# Current_Sensor.net
KiCad netlist of a schematic drawn in Altium Designer
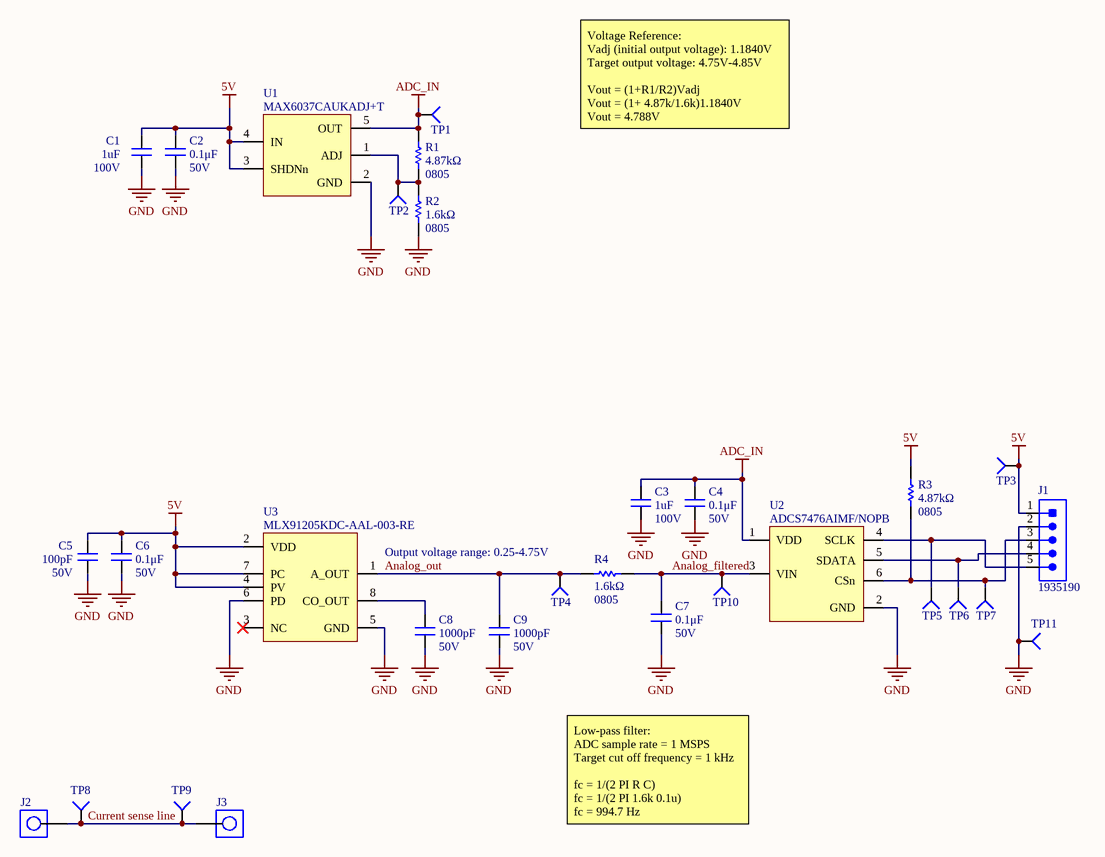
[diagram p0: Current Sensor.SchDoc]

(export (version "E")
  (design (tool "Eeschema 10.0.6"))
  (components
    (comp (ref "C1")
      (value "CAP_1uF_100V_1206")
      (footprint "CAPC3216X190X50NL20T25")
      (description "CAP CER 1UF 100V X7R 1206")
      (fields
        (field (name "MANUFACTURER") "Murata")
        (field (name "MANUFACTURER PART NUMBER") "GCJ31CR72A105KA01L")
        (field (name "CAPACITANCE") "1uF")
        (field (name "VOLTAGE RATING") "100V")
      )
      (libsource (lib "UWRT_Schematic_Library_2020") (part "CAP_1uF_100V_1206"))
    )
    (comp (ref "C2")
      (value "0.1μF")
      (footprint "CAP2012")
      (description "CAP CER 0.1UF 50V X7R 0805")
      (fields (field (name "TOLERANCE") "10%") (field (name "VOLTAGE RATING") "50V"))
      (libsource (lib "UWRT_Schematic_Library_2020") (part "CAP_0.1uF_50V_0805"))
    )
    (comp (ref "C3")
      (value "CAP_1uF_100V_1206")
      (footprint "CAPC3216X190X50NL20T25")
      (description "CAP CER 1UF 100V X7R 1206")
      (fields
        (field (name "MANUFACTURER") "Murata")
        (field (name "MANUFACTURER PART NUMBER") "GCJ31CR72A105KA01L")
        (field (name "CAPACITANCE") "1uF")
        (field (name "VOLTAGE RATING") "100V")
      )
      (libsource (lib "UWRT_Schematic_Library_2020") (part "CAP_1uF_100V_1206"))
    )
    (comp (ref "C4")
      (value "0.1μF")
      (footprint "CAP2012")
      (description "CAP CER 0.1UF 50V X7R 0805")
      (fields (field (name "TOLERANCE") "10%") (field (name "VOLTAGE RATING") "50V"))
      (libsource (lib "UWRT_Schematic_Library_2020") (part "CAP_0.1uF_50V_0805"))
    )
    (comp (ref "C5")
      (value "100pF")
      (footprint "CAP2012")
      (description "CAP CER 100PF 50V C0G/NP0 0805")
      (fields
        (field (name "TOLERANCE") "5%")
        (field (name "VOLTAGE RATING") "50V")
        (field (name "Comment") "CAP_100pF_50V_0805")
      )
      (libsource (lib "UWRT_Schematic_Library_2020") (part "CAP_100pF_50V_0805"))
    )
    (comp (ref "C6")
      (value "0.1μF")
      (footprint "CAP2012")
      (description "CAP CER 0.1UF 50V X7R 0805")
      (fields (field (name "TOLERANCE") "10%") (field (name "VOLTAGE RATING") "50V"))
      (libsource (lib "UWRT_Schematic_Library_2020") (part "CAP_0.1uF_50V_0805"))
    )
    (comp (ref "C7")
      (value "0.1μF")
      (footprint "CAP2012")
      (description "CAP CER 0.1UF 50V X7R 0805")
      (fields (field (name "TOLERANCE") "10%") (field (name "VOLTAGE RATING") "50V"))
      (libsource (lib "UWRT_Schematic_Library_2020") (part "CAP_0.1uF_50V_0805"))
    )
    (comp (ref "C8")
      (value "CAP_1000pF_50V_0805")
      (footprint "CAP2012")
      (description "CAP CER 1000pF 50V X7R 0805")
      (fields
        (field (name "TOLERANCE") "10%")
        (field (name "VOLTAGE") "50V")
        (field (name "VOLTAGE RATING") "50V")
        (field (name "CAPACITANCE") "1000pF")
      )
      (libsource (lib "UWRT_Schematic_Library_2020") (part "CAP_1000pF_50V_0805"))
    )
    (comp (ref "C9")
      (value "CAP_1000pF_50V_0805")
      (footprint "CAP2012")
      (description "CAP CER 1000pF 50V X7R 0805")
      (fields
        (field (name "TOLERANCE") "10%")
        (field (name "VOLTAGE") "50V")
        (field (name "VOLTAGE RATING") "50V")
        (field (name "CAPACITANCE") "1000pF")
      )
      (libsource (lib "UWRT_Schematic_Library_2020") (part "CAP_1000pF_50V_0805"))
    )
    (comp (ref "J1")
      (value "CON_5M_TERM")
      (footprint "1935190")
      (description "Barrier Strip Terminal Block, 17.5A, 1.5mm2, 1 Row(s), 1 Deck(s)")
      (fields (field (name "VOLTAGE") "300V") (field (name "MANUFACTURER PART NUMBER 1") "1935190"))
      (libsource (lib "UWRT_Schematic_Library_2020") (part "CON_5M_TERM"))
    )
    (comp (ref "J2")
      (value "Screw Terminal 6-32")
      (footprint "7701_KEYSTONE")
      (description "TERM W/ASSEMBLD SCREW VERT PCMNT")
      (libsource (lib "UWRT_Schematic_Library_2020") (part "SCREW_TERMINAL_1_POS_6_32"))
    )
    (comp (ref "J3")
      (value "Screw Terminal 6-32")
      (footprint "7701_KEYSTONE")
      (description "TERM W/ASSEMBLD SCREW VERT PCMNT")
      (libsource (lib "UWRT_Schematic_Library_2020") (part "SCREW_TERMINAL_1_POS_6_32"))
    )
    (comp (ref "R1")
      (value "RES_4.87kΩ_0805")
      (footprint "RESC0805(2012)_H")
      (description "RES SMD 4.87k OHM 0.1% 1/8W 0805")
      (fields
        (field (name "TOLERANCE") "0.1%")
        (field (name "CASE CODE (IMPERIAL)") "0805")
        (field (name "RESISTANCE") "4.87kΩ")
      )
      (libsource (lib "UWRT_Schematic_Library_2020") (part "RES_4.87kΩ_0805"))
    )
    (comp (ref "R2")
      (value "RES_1.6kΩ_0805")
      (footprint "RESC0805(2012)_H")
      (description "RES SMD 1.6K OHM 0.1% 1/4W 0805")
      (fields
        (field (name "TOLERANCE") "0.1%")
        (field (name "CASE/PACKAGE") "0805")
        (field (name "RESISTANCE") "1.6kΩ")
      )
      (libsource (lib "UWRT_Schematic_Library_2020") (part "RES_1.6kΩ_0805"))
    )
    (comp (ref "R3")
      (value "RES_4.87kΩ_0805")
      (footprint "RESC0805(2012)_H")
      (description "RES SMD 4.87k OHM 0.1% 1/8W 0805")
      (fields
        (field (name "TOLERANCE") "0.1%")
        (field (name "CASE CODE (IMPERIAL)") "0805")
        (field (name "RESISTANCE") "4.87kΩ")
      )
      (libsource (lib "UWRT_Schematic_Library_2020") (part "RES_4.87kΩ_0805"))
    )
    (comp (ref "R4")
      (value "RES_1.6kΩ_0805")
      (footprint "RESC0805(2012)_H")
      (description "RES SMD 1.6K OHM 0.1% 1/4W 0805")
      (fields
        (field (name "TOLERANCE") "0.1%")
        (field (name "CASE/PACKAGE") "0805")
        (field (name "RESISTANCE") "1.6kΩ")
      )
      (libsource (lib "UWRT_Schematic_Library_2020") (part "RES_1.6kΩ_0805"))
    )
    (comp (ref "TP1")
      (value "TESTPOINT_SMD_LOOP")
      (footprint "S1751-46R")
      (description "PC TEST POINT SMD")
      (libsource (lib "UWRT_Schematic_Library_2020") (part "TESTPOINT_SMD_LOOP"))
    )
    (comp (ref "TP2")
      (value "TESTPOINT_1MM_CIRCLE")
      (footprint "TESTPOINT_CIRCLE_1MM")
      (description "TESTPOINT 1MM CIRCLE")
      (libsource (lib "UWRT_Schematic_Library_2020") (part "TESTPOINT_1MM_CIRCLE"))
    )
    (comp (ref "TP3")
      (value "TESTPOINT_SMD_LOOP")
      (footprint "S1751-46R")
      (description "PC TEST POINT SMD")
      (libsource (lib "UWRT_Schematic_Library_2020") (part "TESTPOINT_SMD_LOOP"))
    )
    (comp (ref "TP4")
      (value "TESTPOINT_1MM_CIRCLE")
      (footprint "TESTPOINT_CIRCLE_1MM")
      (description "TESTPOINT 1MM CIRCLE")
      (libsource (lib "UWRT_Schematic_Library_2020") (part "TESTPOINT_1MM_CIRCLE"))
    )
    (comp (ref "TP5")
      (value "TESTPOINT_1MM_CIRCLE")
      (footprint "TESTPOINT_CIRCLE_1MM")
      (description "TESTPOINT 1MM CIRCLE")
      (libsource (lib "UWRT_Schematic_Library_2020") (part "TESTPOINT_1MM_CIRCLE"))
    )
    (comp (ref "TP6")
      (value "TESTPOINT_1MM_CIRCLE")
      (footprint "TESTPOINT_CIRCLE_1MM")
      (description "TESTPOINT 1MM CIRCLE")
      (libsource (lib "UWRT_Schematic_Library_2020") (part "TESTPOINT_1MM_CIRCLE"))
    )
    (comp (ref "TP7")
      (value "TESTPOINT_1MM_CIRCLE")
      (footprint "TESTPOINT_CIRCLE_1MM")
      (description "TESTPOINT 1MM CIRCLE")
      (libsource (lib "UWRT_Schematic_Library_2020") (part "TESTPOINT_1MM_CIRCLE"))
    )
    (comp (ref "TP8")
      (value "TESTPOINT_SMD_LOOP")
      (footprint "S1751-46R")
      (description "PC TEST POINT SMD")
      (libsource (lib "UWRT_Schematic_Library_2020") (part "TESTPOINT_SMD_LOOP"))
    )
    (comp (ref "TP9")
      (value "TESTPOINT_SMD_LOOP")
      (footprint "S1751-46R")
      (description "PC TEST POINT SMD")
      (libsource (lib "UWRT_Schematic_Library_2020") (part "TESTPOINT_SMD_LOOP"))
    )
    (comp (ref "TP10")
      (value "TESTPOINT_1MM_CIRCLE")
      (footprint "TESTPOINT_CIRCLE_1MM")
      (description "TESTPOINT 1MM CIRCLE")
      (libsource (lib "UWRT_Schematic_Library_2020") (part "TESTPOINT_1MM_CIRCLE"))
    )
    (comp (ref "TP11")
      (value "TESTPOINT_1MM_SQUARE")
      (footprint "TESTPOINT_SQUARE_1MM")
      (description "TESTPOINT 1MM SQUARE")
      (libsource (lib "UWRT_Schematic_Library_2020") (part "TESTPOINT_1MM_SQUARE"))
    )
    (comp (ref "U1")
      (value "MAX6037CAUKADJ+T")
      (footprint "SOT23-5")
      (description "Three Terminal Voltage Reference, 1 Output, Trim/Adjustable, BICMOS, PDSO5")
      (fields
        (field (name "TOLERANCE") "0.5%")
        (field (name "MANUFACTURER PART NUMBER 1") "MAX6037CAUKADJ+T")
      )
      (libsource (lib "UWRT_Schematic_Library_2020") (part "MAX6037CAUKADJ+T"))
    )
    (comp (ref "U2")
      (value "ADCS7476AIMF/NOPB")
      (footprint "ADCS747x")
      (description "1-Channel Single ADC SAR 1Msps 12-bit Serial 6-Pin SOT-23 T/R")
      (fields (field (name "MANUFACTURER PART NUMBER 1") "ADCS7476AIMF/NOPB"))
      (libsource (lib "UWRT_Schematic_Library_2020") (part "ADCS7476AIMF/NOPB"))
    )
    (comp (ref "U3")
      (value "MLX91205KDC-AAL-003-RE")
      (footprint "8-SOIC_M")
      (description "Analog Circuit, 1 Func, PDSO8")
      (fields (field (name "MANUFACTURER PART NUMBER 1") "MLX91205KDC-AAL-003-RE"))
      (libsource (lib "UWRT_Schematic_Library_2020") (part "MLX91205KDC-AAL-003-RE"))
    )
  )
  (nets
    (net (code "1") (name "/Analog_filtered") (class "Default")
      (node (ref "C7") (pin "2") (pinfunction "2_2") (pintype "passive"))
      (node (ref "R4") (pin "1") (pinfunction "1_1") (pintype "passive"))
      (node (ref "TP10") (pin "1") (pinfunction "=value_1") (pintype "passive"))
      (node (ref "U2") (pin "3") (pinfunction "VIN_3") (pintype "passive"))
    )
    (net (code "2") (name "/Analog_out") (class "Default")
      (node (ref "C9") (pin "2") (pinfunction "2_2") (pintype "passive"))
      (node (ref "R4") (pin "2") (pinfunction "2_2") (pintype "passive"))
      (node (ref "TP4") (pin "1") (pinfunction "=value_1") (pintype "passive"))
      (node (ref "U3") (pin "1") (pinfunction "A_OUT_1") (pintype "passive"))
    )
    (net (code "3") (name "/Current sense line") (class "Default")
      (node (ref "J2") (pin "1") (pinfunction "1_1") (pintype "passive"))
      (node (ref "J3") (pin "1") (pinfunction "1_1") (pintype "passive"))
      (node (ref "TP8") (pin "1") (pinfunction "=value_1") (pintype "passive"))
      (node (ref "TP9") (pin "1") (pinfunction "=value_1") (pintype "passive"))
    )
    (net (code "4") (name "5V") (class "Default")
      (node (ref "C1") (pin "2") (pinfunction "2_2") (pintype "passive"))
      (node (ref "C2") (pin "2") (pinfunction "2_2") (pintype "passive"))
      (node (ref "C5") (pin "2") (pinfunction "2_2") (pintype "passive"))
      (node (ref "C6") (pin "2") (pinfunction "2_2") (pintype "passive"))
      (node (ref "J1") (pin "1") (pinfunction "1_1") (pintype "passive"))
      (node (ref "R3") (pin "2") (pinfunction "2_2") (pintype "passive"))
      (node (ref "TP3") (pin "1") (pinfunction "=value_1") (pintype "passive"))
      (node (ref "U1") (pin "3") (pinfunction "SHDNn_3") (pintype "passive"))
      (node (ref "U1") (pin "4") (pinfunction "IN_4") (pintype "passive"))
      (node (ref "U3") (pin "2") (pinfunction "VDD_2") (pintype "passive"))
      (node (ref "U3") (pin "4") (pinfunction "PV_4") (pintype "passive"))
      (node (ref "U3") (pin "7") (pinfunction "PC_7") (pintype "passive"))
    )
    (net (code "5") (name "ADC_IN") (class "Default")
      (node (ref "C3") (pin "2") (pinfunction "2_2") (pintype "passive"))
      (node (ref "C4") (pin "2") (pinfunction "2_2") (pintype "passive"))
      (node (ref "R1") (pin "2") (pinfunction "2_2") (pintype "passive"))
      (node (ref "TP1") (pin "1") (pinfunction "=value_1") (pintype "passive"))
      (node (ref "U1") (pin "5") (pinfunction "OUT_5") (pintype "passive"))
      (node (ref "U2") (pin "1") (pinfunction "VDD_1") (pintype "passive"))
    )
    (net (code "6") (name "GND") (class "Default")
      (node (ref "C1") (pin "1") (pinfunction "1_1") (pintype "passive"))
      (node (ref "C2") (pin "1") (pinfunction "1_1") (pintype "passive"))
      (node (ref "C3") (pin "1") (pinfunction "1_1") (pintype "passive"))
      (node (ref "C4") (pin "1") (pinfunction "1_1") (pintype "passive"))
      (node (ref "C5") (pin "1") (pinfunction "1_1") (pintype "passive"))
      (node (ref "C6") (pin "1") (pinfunction "1_1") (pintype "passive"))
      (node (ref "C7") (pin "1") (pinfunction "1_1") (pintype "passive"))
      (node (ref "C8") (pin "1") (pinfunction "1_1") (pintype "passive"))
      (node (ref "C9") (pin "1") (pinfunction "1_1") (pintype "passive"))
      (node (ref "J1") (pin "2") (pinfunction "2_2") (pintype "passive"))
      (node (ref "R2") (pin "1") (pinfunction "1_1") (pintype "passive"))
      (node (ref "TP11") (pin "1") (pinfunction "=value_1") (pintype "passive"))
      (node (ref "U1") (pin "2") (pinfunction "GND_2") (pintype "passive"))
      (node (ref "U2") (pin "2") (pinfunction "GND_2") (pintype "passive"))
      (node (ref "U3") (pin "5") (pinfunction "GND_5") (pintype "passive"))
      (node (ref "U3") (pin "6") (pinfunction "PD_6") (pintype "passive"))
    )
    (net (code "7") (name "Net-(TP2-=value)") (class "Default")
      (node (ref "R1") (pin "1") (pinfunction "1_1") (pintype "passive"))
      (node (ref "R2") (pin "2") (pinfunction "2_2") (pintype "passive"))
      (node (ref "TP2") (pin "1") (pinfunction "=value_1") (pintype "passive"))
      (node (ref "U1") (pin "1") (pinfunction "ADJ_1") (pintype "passive"))
    )
    (net (code "8") (name "Net-(TP5-=value)") (class "Default")
      (node (ref "J1") (pin "5") (pinfunction "5_5") (pintype "passive"))
      (node (ref "TP5") (pin "1") (pinfunction "=value_1") (pintype "passive"))
      (node (ref "U2") (pin "4") (pinfunction "SCLK_4") (pintype "passive"))
    )
    (net (code "9") (name "Net-(TP6-=value)") (class "Default")
      (node (ref "J1") (pin "4") (pinfunction "4_4") (pintype "passive"))
      (node (ref "TP6") (pin "1") (pinfunction "=value_1") (pintype "passive"))
      (node (ref "U2") (pin "5") (pinfunction "SDATA_5") (pintype "passive"))
    )
    (net (code "10") (name "Net-(TP7-=value)") (class "Default")
      (node (ref "J1") (pin "3") (pinfunction "3_3") (pintype "passive"))
      (node (ref "R3") (pin "1") (pinfunction "1_1") (pintype "passive"))
      (node (ref "TP7") (pin "1") (pinfunction "=value_1") (pintype "passive"))
      (node (ref "U2") (pin "6") (pinfunction "CSn_6") (pintype "passive"))
    )
    (net (code "11") (name "Net-(U3-CO_OUT)") (class "Default")
      (node (ref "C8") (pin "2") (pinfunction "2_2") (pintype "passive"))
      (node (ref "U3") (pin "8") (pinfunction "CO_OUT_8") (pintype "passive"))
    )
    (net (code "12") (name "unconnected-(U3-NC-Pad3)") (class "Default")
      (node (ref "U3") (pin "3") (pinfunction "NC_3") (pintype "passive+no_connect"))
    )
  )
)
